# sensorinterface.net
KiCad netlist of a schematic drawn in Altium Designer
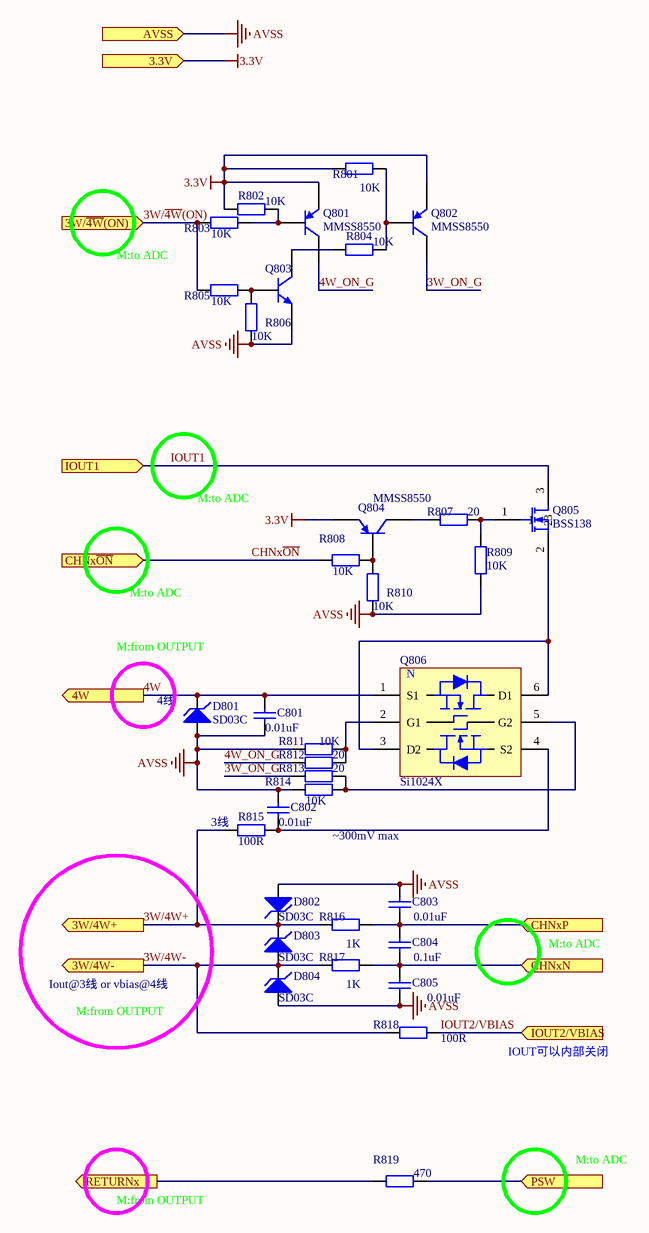
[diagram p0: sensorinterface.SchDoc]

(export (version "E")
  (design (tool "Eeschema 10.0.6"))
  (components
    (comp (ref "C801")
      (value "0.01uF")
      (footprint "0603C")
      (description "Capacitor")
      (fields (field (name "Comment") "CC0805MRX7R9BB103") (field (name "PUBLISHER") "Altium Limited"))
      (libsource (lib "Miscellaneous Devices") (part "Cap"))
    )
    (comp (ref "C802")
      (value "0.01uF")
      (footprint "0603C")
      (description "Capacitor")
      (fields (field (name "Comment") "CC0805MRX7R9BB103") (field (name "PUBLISHER") "Altium Limited"))
      (libsource (lib "Miscellaneous Devices") (part "Cap"))
    )
    (comp (ref "C803")
      (value "0.01uF")
      (footprint "0603C")
      (description "Capacitor")
      (fields (field (name "Comment") "CC0805MRX7R9BB103") (field (name "PUBLISHER") "Altium Limited"))
      (libsource (lib "Miscellaneous Devices") (part "Cap"))
    )
    (comp (ref "C804")
      (value "0.1uF")
      (footprint "0603C")
      (description "Capacitor")
      (fields (field (name "Comment") "CC0805MRX7R9BB104") (field (name "PUBLISHER") "Altium Limited"))
      (libsource (lib "Miscellaneous Devices") (part "Cap"))
    )
    (comp (ref "C805")
      (value "0.01uF")
      (footprint "0603C")
      (description "Capacitor")
      (fields (field (name "Comment") "CC0805MRX7R9BB103") (field (name "PUBLISHER") "Altium Limited"))
      (libsource (lib "Miscellaneous Devices") (part "Cap"))
    )
    (comp (ref "D801")
      (value "SD03C")
      (footprint "sod323")
      (libsource (lib "Standard-V0.0") (part "TVS DIODE"))
    )
    (comp (ref "D802")
      (value "SD03C")
      (footprint "sod323")
      (libsource (lib "Standard-V0.0") (part "TVS DIODE"))
    )
    (comp (ref "D803")
      (value "SD03C")
      (footprint "sod323")
      (libsource (lib "Standard-V0.0") (part "TVS DIODE"))
    )
    (comp (ref "D804")
      (value "SD03C")
      (footprint "sod323")
      (libsource (lib "Standard-V0.0") (part "TVS DIODE"))
    )
    (comp (ref "Q801")
      (value "MMSS8550")
      (footprint "SOT-23")
      (description "PNP Bipolar Transistor")
      (fields (field (name "PUBLISHER") "Altium Limited"))
      (libsource (lib "Miscellaneous Devices") (part "PNP"))
    )
    (comp (ref "Q802")
      (value "MMSS8550")
      (footprint "SOT-23")
      (description "PNP Bipolar Transistor")
      (fields (field (name "PUBLISHER") "Altium Limited"))
      (libsource (lib "Miscellaneous Devices") (part "PNP"))
    )
    (comp (ref "Q803")
      (value "MMSS8050")
      (footprint "SOT-23")
      (description "NPN Bipolar Transistor")
      (fields (field (name "PUBLISHER") "Altium Limited"))
      (libsource (lib "Miscellaneous Devices") (part "NPN"))
    )
    (comp (ref "Q804")
      (value "MMSS8550")
      (footprint "SOT-23")
      (description "PNP Bipolar Transistor")
      (fields (field (name "PUBLISHER") "Altium Limited"))
      (libsource (lib "Miscellaneous Devices") (part "PNP"))
    )
    (comp (ref "Q805")
      (value "BSS138")
      (footprint "SOT-23(SS8050)")
      (description "N-Channel MOSFET")
      (fields (field (name "PUBLISHER") "Altium Limited"))
      (libsource (lib "Miscellaneous Devices") (part "MOSFET-N"))
    )
    (comp (ref "Q806")
      (value "Si1024X")
      (footprint "SOT563")
      (libsource (lib "Standard-V0.0") (part "Si1024X"))
    )
    (comp (ref "R801")
      (value "10K")
      (footprint "0603R")
      (description "Resistor")
      (fields (field (name "Comment") "RC0805JR-0710KL") (field (name "PUBLISHER") "Altium Limited"))
      (libsource (lib "Miscellaneous Devices") (part "Res2"))
    )
    (comp (ref "R802")
      (value "10K")
      (footprint "0603R")
      (description "Resistor")
      (fields (field (name "Comment") "RC0805JR-0710KL") (field (name "PUBLISHER") "Altium Limited"))
      (libsource (lib "Miscellaneous Devices") (part "Res2"))
    )
    (comp (ref "R803")
      (value "10K")
      (footprint "0603R")
      (description "Resistor")
      (fields (field (name "Comment") "RC0805JR-0710KL") (field (name "PUBLISHER") "Altium Limited"))
      (libsource (lib "Miscellaneous Devices") (part "Res2"))
    )
    (comp (ref "R804")
      (value "10K")
      (footprint "0603R")
      (description "Resistor")
      (fields (field (name "Comment") "RC0805JR-0710KL") (field (name "PUBLISHER") "Altium Limited"))
      (libsource (lib "Miscellaneous Devices") (part "Res2"))
    )
    (comp (ref "R805")
      (value "10K")
      (footprint "0603R")
      (description "Resistor")
      (fields (field (name "Comment") "RC0805JR-0710KL") (field (name "PUBLISHER") "Altium Limited"))
      (libsource (lib "Miscellaneous Devices") (part "Res2"))
    )
    (comp (ref "R806")
      (value "10K")
      (footprint "0603R")
      (description "Resistor")
      (fields (field (name "Comment") "RC0805JR-0710KL") (field (name "PUBLISHER") "Altium Limited"))
      (libsource (lib "") (part "Res2_2"))
    )
    (comp (ref "R807")
      (value "20")
      (footprint "0603R")
      (description "Resistor")
      (fields (field (name "Comment") "RC0805JR-0720RL") (field (name "PUBLISHER") "Altium Limited"))
      (libsource (lib "") (part "Res2_1"))
    )
    (comp (ref "R808")
      (value "10K")
      (footprint "0603R")
      (description "Resistor")
      (fields (field (name "Comment") "RC0805JR-0710KL") (field (name "PUBLISHER") "Altium Limited"))
      (libsource (lib "Miscellaneous Devices") (part "Res2"))
    )
    (comp (ref "R809")
      (value "10K")
      (footprint "0603R")
      (description "Resistor")
      (fields (field (name "Comment") "RC0805JR-0710KL") (field (name "PUBLISHER") "Altium Limited"))
      (libsource (lib "") (part "Res2_2"))
    )
    (comp (ref "R810")
      (value "10K")
      (footprint "0603R")
      (description "Resistor")
      (fields (field (name "Comment") "RC0805JR-0710KL") (field (name "PUBLISHER") "Altium Limited"))
      (libsource (lib "") (part "Res2_2"))
    )
    (comp (ref "R811")
      (value "10K")
      (footprint "0603R")
      (description "Resistor")
      (fields (field (name "Comment") "RC0805JR-0710KL") (field (name "PUBLISHER") "Altium Limited"))
      (libsource (lib "") (part "Res2_1"))
    )
    (comp (ref "R812")
      (value "20")
      (footprint "0603R")
      (description "Resistor")
      (fields (field (name "Comment") "RC0805JR-0720RL") (field (name "PUBLISHER") "Altium Limited"))
      (libsource (lib "") (part "Res2_1"))
    )
    (comp (ref "R813")
      (value "20")
      (footprint "0603R")
      (description "Resistor")
      (fields (field (name "Comment") "RC0805JR-0720RL") (field (name "PUBLISHER") "Altium Limited"))
      (libsource (lib "") (part "Res2_1"))
    )
    (comp (ref "R814")
      (value "10K")
      (footprint "0603R")
      (description "Resistor")
      (fields (field (name "Comment") "RC0805JR-0710KL") (field (name "PUBLISHER") "Altium Limited"))
      (libsource (lib "") (part "Res2_1"))
    )
    (comp (ref "R815")
      (value "100R")
      (footprint "0603R")
      (description "Resistor")
      (fields (field (name "Comment") "RC0805JR-07100RL") (field (name "PUBLISHER") "Altium Limited"))
      (libsource (lib "") (part "Res2_1"))
    )
    (comp (ref "R816")
      (value "1K")
      (footprint "0603R")
      (description "Resistor")
      (fields (field (name "Comment") "RC0805JR-071KL") (field (name "PUBLISHER") "Altium Limited"))
      (libsource (lib "Miscellaneous Devices") (part "Res2"))
    )
    (comp (ref "R817")
      (value "1K")
      (footprint "0603R")
      (description "Resistor")
      (fields (field (name "Comment") "RC0805JR-071KL") (field (name "PUBLISHER") "Altium Limited"))
      (libsource (lib "Miscellaneous Devices") (part "Res2"))
    )
    (comp (ref "R818")
      (value "100R")
      (footprint "0603R")
      (description "Resistor")
      (fields (field (name "Comment") "RC0805JR-07100RL") (field (name "PUBLISHER") "Altium Limited"))
      (libsource (lib "Miscellaneous Devices") (part "Res2"))
    )
    (comp (ref "R819")
      (value "470")
      (footprint "0603R")
      (description "Resistor")
      (fields (field (name "Comment") "RC0805JR-07470RL") (field (name "PUBLISHER") "Altium Limited"))
      (libsource (lib "Miscellaneous Devices") (part "Res2"))
    )
  )
  (nets
    (net (code "1") (name "/3W_ON_G") (class "Default")
      (node (ref "Q802") (pin "1") (pinfunction "C_1") (pintype "passive"))
      (node (ref "R813") (pin "1") (pinfunction "1_1") (pintype "passive"))
    )
    (net (code "2") (name "/3W{slash}4W+") (class "Default")
      (node (ref "D802") (pin "2") (pinfunction "CATHODE_2") (pintype "passive"))
      (node (ref "D803") (pin "2") (pinfunction "CATHODE_2") (pintype "passive"))
      (node (ref "R815") (pin "1") (pinfunction "1_1") (pintype "passive"))
      (node (ref "R816") (pin "2") (pinfunction "2_2") (pintype "passive"))
    )
    (net (code "3") (name "/3W{slash}4W-") (class "Default")
      (node (ref "D803") (pin "1") (pinfunction "ANODE_1") (pintype "passive"))
      (node (ref "D804") (pin "2") (pinfunction "CATHODE_2") (pintype "passive"))
      (node (ref "R817") (pin "2") (pinfunction "2_2") (pintype "passive"))
      (node (ref "R818") (pin "2") (pinfunction "2_2") (pintype "passive"))
    )
    (net (code "4") (name "/3W{slash}~{4W}(ON)") (class "Default")
      (node (ref "R803") (pin "2") (pinfunction "2_2") (pintype "passive"))
      (node (ref "R805") (pin "2") (pinfunction "2_2") (pintype "passive"))
    )
    (net (code "5") (name "/4W") (class "Default")
      (node (ref "C801") (pin "1") (pinfunction "1_1") (pintype "passive"))
      (node (ref "D801") (pin "2") (pinfunction "CATHODE_2") (pintype "passive"))
      (node (ref "Q806") (pin "1") (pinfunction "S1_1") (pintype "passive"))
    )
    (net (code "6") (name "/4W_ON_G") (class "Default")
      (node (ref "Q801") (pin "1") (pinfunction "C_1") (pintype "passive"))
      (node (ref "R812") (pin "1") (pinfunction "1_1") (pintype "passive"))
    )
    (net (code "7") (name "/CHNxN") (class "Default")
      (node (ref "C804") (pin "2") (pinfunction "2_2") (pintype "passive"))
      (node (ref "C805") (pin "1") (pinfunction "1_1") (pintype "passive"))
      (node (ref "R817") (pin "1") (pinfunction "1_1") (pintype "passive"))
    )
    (net (code "8") (name "/CHNxP") (class "Default")
      (node (ref "C803") (pin "1") (pinfunction "1_1") (pintype "passive"))
      (node (ref "C804") (pin "1") (pinfunction "1_1") (pintype "passive"))
      (node (ref "R816") (pin "1") (pinfunction "1_1") (pintype "passive"))
    )
    (net (code "9") (name "/CHNx~{ON}") (class "Default")
      (node (ref "R808") (pin "2") (pinfunction "2_2") (pintype "passive"))
    )
    (net (code "10") (name "/IOUT1") (class "Default")
      (node (ref "Q805") (pin "3") (pinfunction "3_3") (pintype "passive"))
    )
    (net (code "11") (name "/IOUT2{slash}VBIAS") (class "Default")
      (node (ref "R818") (pin "1") (pinfunction "1_1") (pintype "passive"))
    )
    (net (code "12") (name "/PSW") (class "Default")
      (node (ref "R819") (pin "1") (pinfunction "1_1") (pintype "passive"))
    )
    (net (code "13") (name "/RETURNx") (class "Default")
      (node (ref "R819") (pin "2") (pinfunction "2_2") (pintype "passive"))
    )
    (net (code "14") (name "3.3V") (class "Default")
      (node (ref "Q801") (pin "3") (pinfunction "E_3") (pintype "passive"))
      (node (ref "Q802") (pin "3") (pinfunction "E_3") (pintype "passive"))
      (node (ref "Q804") (pin "3") (pinfunction "E_3") (pintype "passive"))
      (node (ref "R801") (pin "2") (pinfunction "2_2") (pintype "passive"))
      (node (ref "R802") (pin "2") (pinfunction "2_2") (pintype "passive"))
    )
    (net (code "15") (name "AVSS") (class "Default")
      (node (ref "C801") (pin "2") (pinfunction "2_2") (pintype "passive"))
      (node (ref "C802") (pin "1") (pinfunction "1_1") (pintype "passive"))
      (node (ref "C803") (pin "2") (pinfunction "2_2") (pintype "passive"))
      (node (ref "C805") (pin "2") (pinfunction "2_2") (pintype "passive"))
      (node (ref "D801") (pin "1") (pinfunction "ANODE_1") (pintype "passive"))
      (node (ref "D802") (pin "1") (pinfunction "ANODE_1") (pintype "passive"))
      (node (ref "D804") (pin "1") (pinfunction "ANODE_1") (pintype "passive"))
      (node (ref "Q803") (pin "3") (pinfunction "E_3") (pintype "passive"))
      (node (ref "R806") (pin "2") (pinfunction "2_2") (pintype "passive"))
      (node (ref "R809") (pin "2") (pinfunction "2_2") (pintype "passive"))
      (node (ref "R810") (pin "2") (pinfunction "2_2") (pintype "passive"))
      (node (ref "R811") (pin "1") (pinfunction "1_1") (pintype "passive"))
      (node (ref "R814") (pin "1") (pinfunction "1_1") (pintype "passive"))
    )
    (net (code "16") (name "Net-(Q801-B)") (class "Default")
      (node (ref "Q801") (pin "2") (pinfunction "B_2") (pintype "passive"))
      (node (ref "R802") (pin "1") (pinfunction "1_1") (pintype "passive"))
      (node (ref "R803") (pin "1") (pinfunction "1_1") (pintype "passive"))
    )
    (net (code "17") (name "Net-(Q802-B)") (class "Default")
      (node (ref "Q802") (pin "2") (pinfunction "B_2") (pintype "passive"))
      (node (ref "R801") (pin "1") (pinfunction "1_1") (pintype "passive"))
      (node (ref "R804") (pin "1") (pinfunction "1_1") (pintype "passive"))
    )
    (net (code "18") (name "Net-(Q803-B)") (class "Default")
      (node (ref "Q803") (pin "2") (pinfunction "B_2") (pintype "passive"))
      (node (ref "R805") (pin "1") (pinfunction "1_1") (pintype "passive"))
      (node (ref "R806") (pin "1") (pinfunction "1_1") (pintype "passive"))
    )
    (net (code "19") (name "Net-(Q803-C)") (class "Default")
      (node (ref "Q803") (pin "1") (pinfunction "C_1") (pintype "passive"))
      (node (ref "R804") (pin "2") (pinfunction "2_2") (pintype "passive"))
    )
    (net (code "20") (name "Net-(Q804-B)") (class "Default")
      (node (ref "Q804") (pin "2") (pinfunction "B_2") (pintype "passive"))
      (node (ref "R808") (pin "1") (pinfunction "1_1") (pintype "passive"))
      (node (ref "R810") (pin "1") (pinfunction "1_1") (pintype "passive"))
    )
    (net (code "21") (name "Net-(Q804-C)") (class "Default")
      (node (ref "Q804") (pin "1") (pinfunction "C_1") (pintype "passive"))
      (node (ref "R807") (pin "1") (pinfunction "1_1") (pintype "passive"))
    )
    (net (code "22") (name "Net-(Q805-Pad1)") (class "Default")
      (node (ref "Q805") (pin "1") (pinfunction "1_1") (pintype "passive"))
      (node (ref "R807") (pin "2") (pinfunction "2_2") (pintype "passive"))
      (node (ref "R809") (pin "1") (pinfunction "1_1") (pintype "passive"))
    )
    (net (code "23") (name "Net-(Q806-D1)") (class "Default")
      (node (ref "Q805") (pin "2") (pinfunction "2_2") (pintype "passive"))
      (node (ref "Q806") (pin "3") (pinfunction "D2_3") (pintype "passive"))
      (node (ref "Q806") (pin "6") (pinfunction "D1_6") (pintype "passive"))
    )
    (net (code "24") (name "Net-(Q806-G1)") (class "Default")
      (node (ref "Q806") (pin "2") (pinfunction "G1_2") (pintype "passive"))
      (node (ref "R811") (pin "2") (pinfunction "2_2") (pintype "passive"))
      (node (ref "R812") (pin "2") (pinfunction "2_2") (pintype "passive"))
    )
    (net (code "25") (name "Net-(Q806-G2)") (class "Default")
      (node (ref "Q806") (pin "5") (pinfunction "G2_5") (pintype "passive"))
      (node (ref "R813") (pin "2") (pinfunction "2_2") (pintype "passive"))
      (node (ref "R814") (pin "2") (pinfunction "2_2") (pintype "passive"))
    )
    (net (code "26") (name "Net-(Q806-S2)") (class "Default")
      (node (ref "C802") (pin "2") (pinfunction "2_2") (pintype "passive"))
      (node (ref "Q806") (pin "4") (pinfunction "S2_4") (pintype "passive"))
      (node (ref "R815") (pin "2") (pinfunction "2_2") (pintype "passive"))
    )
  )
)
